# samd21_sensorhub_1_1_jan2022.net
KiCad netlist of a schematic drawn in EAGLE
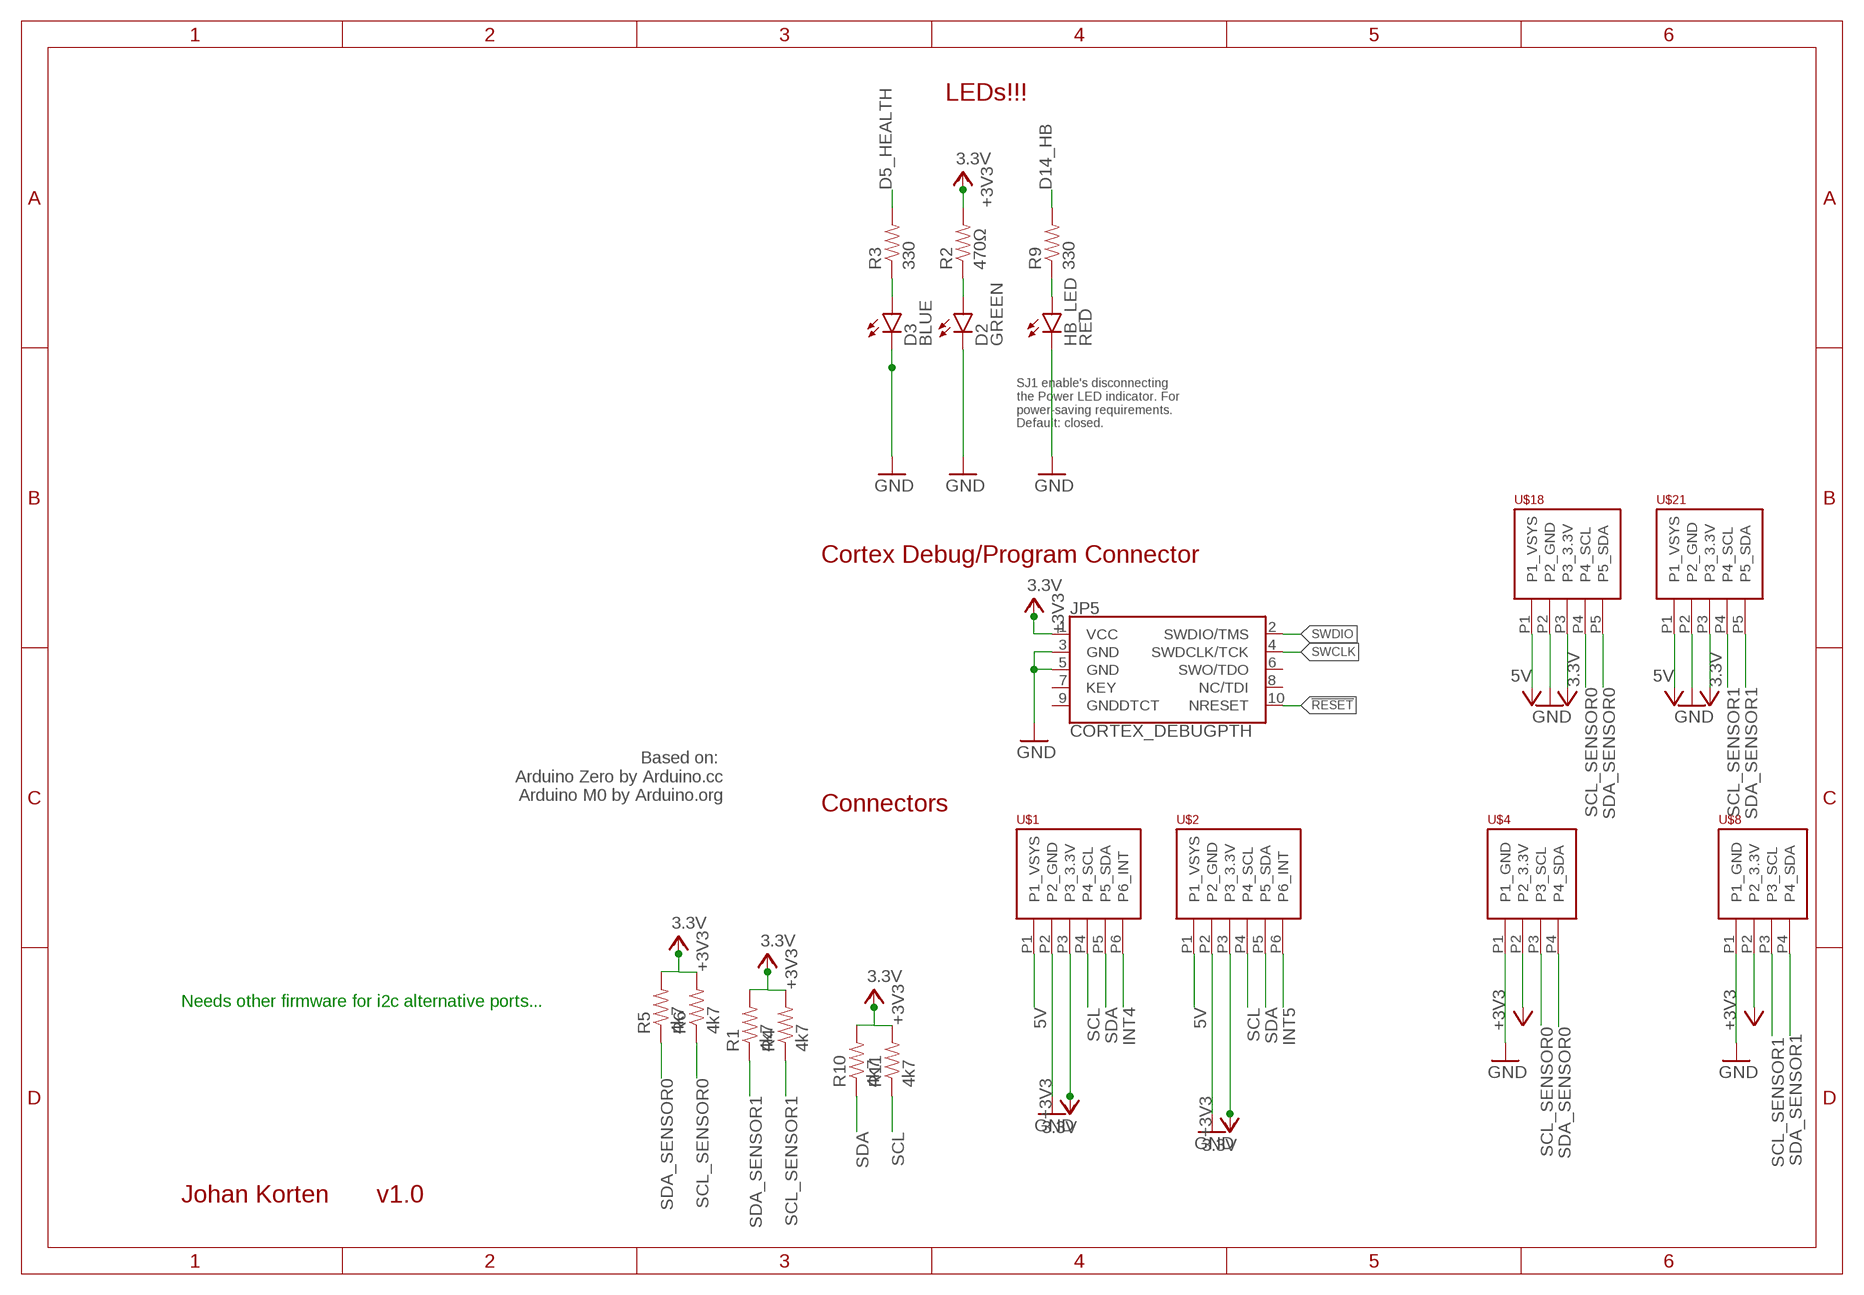
[diagram p0: schematic, sheet 1]
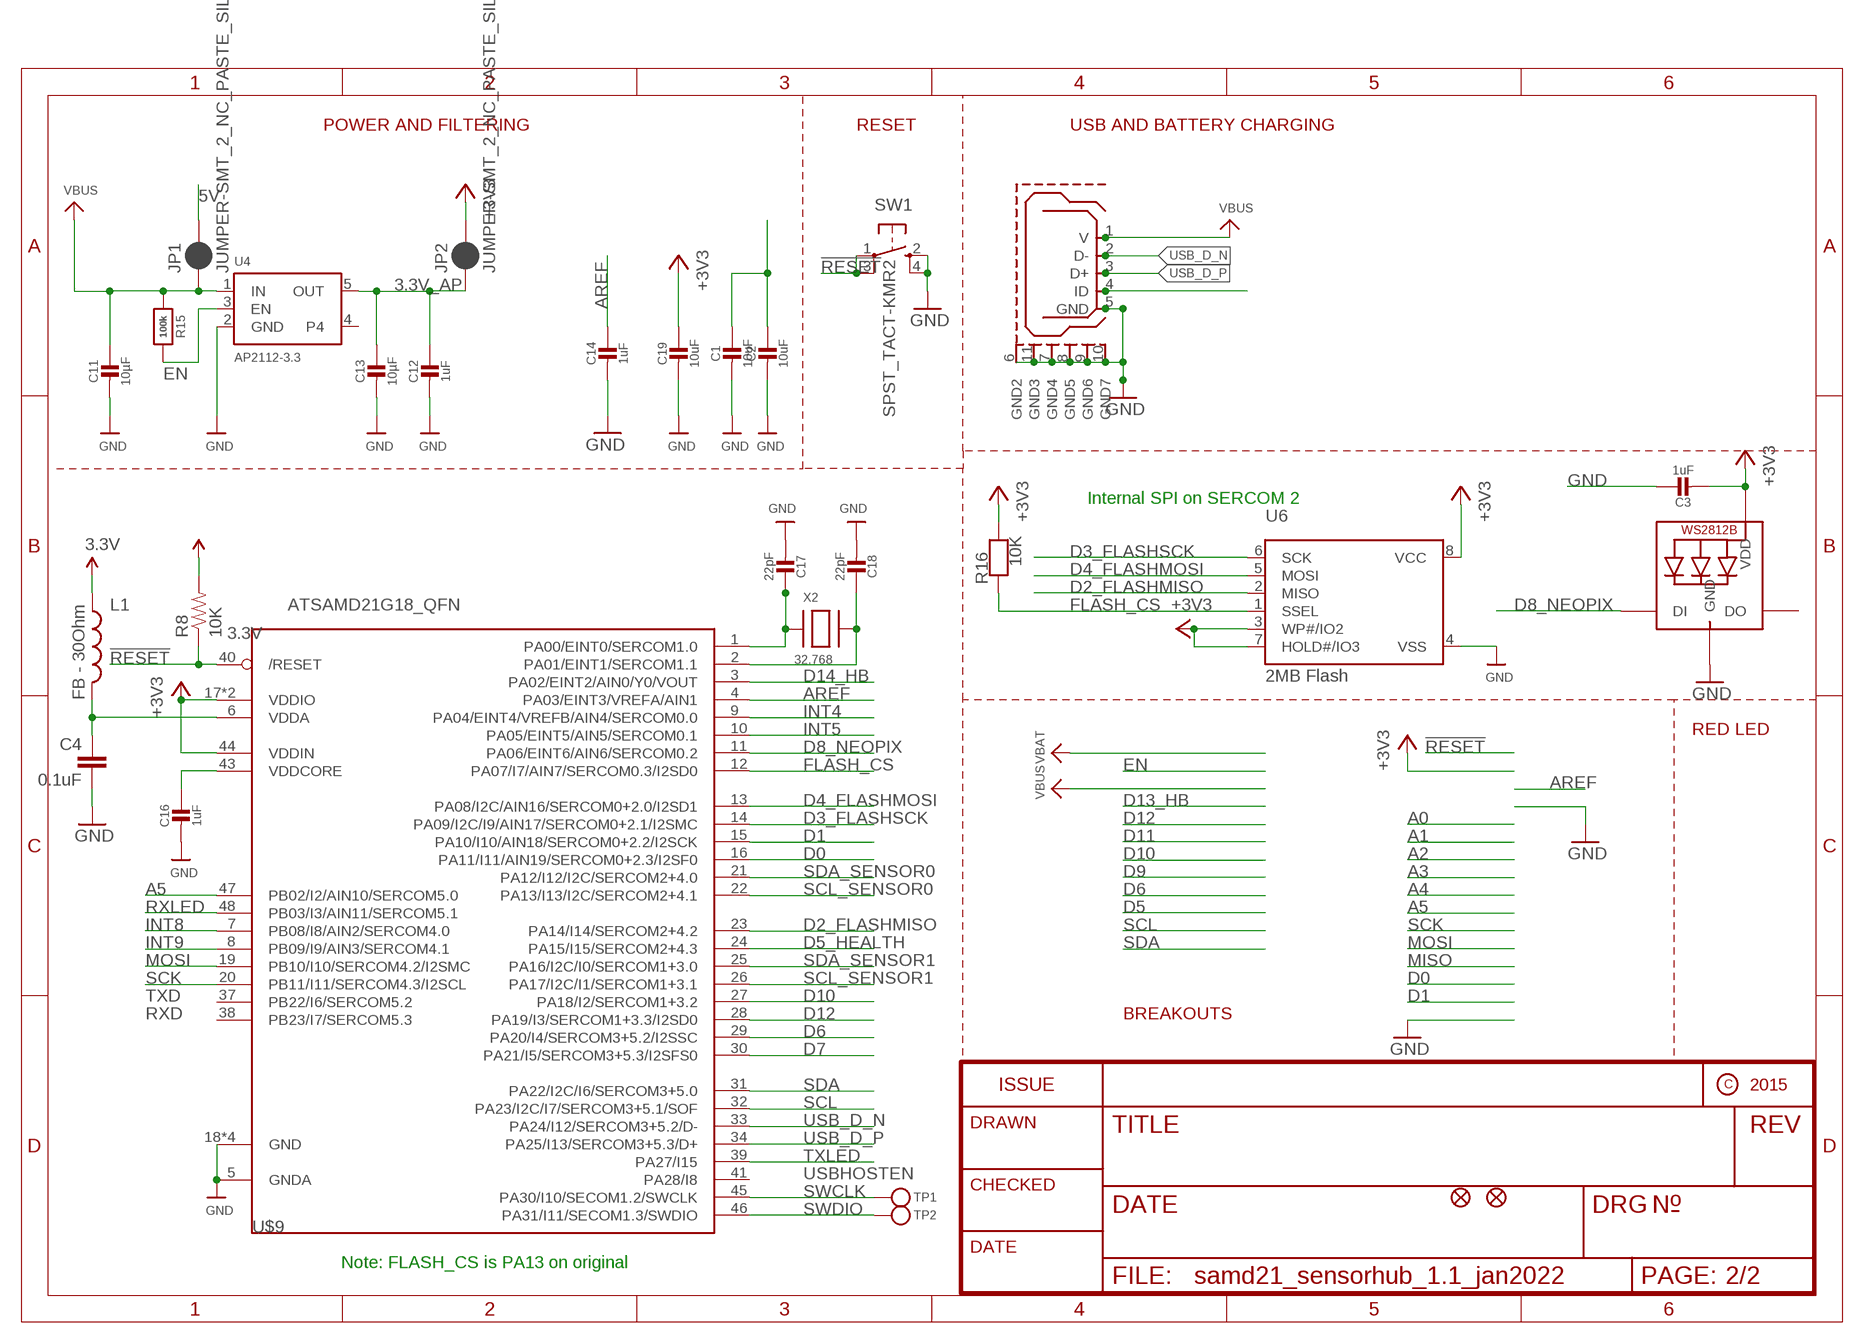
[diagram p1: schematic, sheet 2]

(export (version "E")
  (design (tool "Eeschema 10.0.6"))
  (components
    (comp (ref "D2")
      (value "GREEN")
      (footprint "eagle-import:LED-0603")
      (libsource (lib "eagle-import") (part "LED-RED0603"))
    )
    (comp (ref "D3")
      (value "BLUE")
      (footprint "eagle-import:LED-0603")
      (libsource (lib "eagle-import") (part "LED-BLUE0603"))
    )
    (comp (ref "HB_LED")
      (value "RED")
      (footprint "eagle-import:LED-0603")
      (libsource (lib "eagle-import") (part "LED-RED0603"))
    )
    (comp (ref "JP5")
      (value "CORTEX_DEBUGPTH")
      (footprint "eagle-import:2X5-PTH-1.27MM")
      (libsource (lib "eagle-import") (part "CORTEX_DEBUGPTH"))
    )
    (comp (ref "R1")
      (value "4k7")
      (footprint "eagle-import:0603-RES")
      (libsource (lib "eagle-import") (part "330OHM1/10W1%(0603)"))
    )
    (comp (ref "R2")
      (value "470Ω")
      (footprint "eagle-import:0603-RES")
      (libsource (lib "eagle-import") (part "330OHM1/10W1%(0603)"))
    )
    (comp (ref "R3")
      (value "330")
      (footprint "eagle-import:0603-RES")
      (libsource (lib "eagle-import") (part "330OHM1/10W1%(0603)"))
    )
    (comp (ref "R4")
      (value "4k7")
      (footprint "eagle-import:0603-RES")
      (libsource (lib "eagle-import") (part "330OHM1/10W1%(0603)"))
    )
    (comp (ref "R5")
      (value "4k7")
      (footprint "eagle-import:0603-RES")
      (libsource (lib "eagle-import") (part "330OHM1/10W1%(0603)"))
    )
    (comp (ref "R6")
      (value "4k7")
      (footprint "eagle-import:0603-RES")
      (libsource (lib "eagle-import") (part "330OHM1/10W1%(0603)"))
    )
    (comp (ref "R9")
      (value "330")
      (footprint "eagle-import:0603-RES")
      (libsource (lib "eagle-import") (part "330OHM1/10W1%(0603)"))
    )
    (comp (ref "R10")
      (value "4k7")
      (footprint "eagle-import:0603-RES")
      (libsource (lib "eagle-import") (part "330OHM1/10W1%(0603)"))
    )
    (comp (ref "R11")
      (value "4k7")
      (footprint "eagle-import:0603-RES")
      (libsource (lib "eagle-import") (part "330OHM1/10W1%(0603)"))
    )
    (comp (ref "U$1")
      (value "PHOENIX_PTSM_M6_TH_I2CPPANGLE")
      (footprint "eagle-import:PTSM_M6_THRHOLE")
      (libsource (lib "eagle-import") (part "PHOENIX_PTSM_M6_TH_I2CPPANGLE"))
    )
    (comp (ref "U$2")
      (value "PHOENIX_PTSM_M6_TH_I2CPPANGLE")
      (footprint "eagle-import:PTSM_M6_THRHOLE")
      (libsource (lib "eagle-import") (part "PHOENIX_PTSM_M6_TH_I2CPPANGLE"))
    )
    (comp (ref "U$4")
      (value "PHOENIX_PTSM_M4_THANGLE")
      (footprint "eagle-import:PTSM_M4_TH")
      (libsource (lib "eagle-import") (part "PHOENIX_PTSM_M4_THANGLE"))
    )
    (comp (ref "U$8")
      (value "PHOENIX_PTSM_M4_THANGLE")
      (footprint "eagle-import:PTSM_M4_TH")
      (libsource (lib "eagle-import") (part "PHOENIX_PTSM_M4_THANGLE"))
    )
    (comp (ref "U$18")
      (value "PHOENIX_PTSM_M5_TH_I2C++")
      (footprint "eagle-import:PTSM_M5_THRHOLE")
      (libsource (lib "eagle-import") (part "PHOENIX_PTSM_M5_TH_I2C++"))
    )
    (comp (ref "U$21")
      (value "PHOENIX_PTSM_M5_TH_I2C++")
      (footprint "eagle-import:PTSM_M5_THRHOLE")
      (libsource (lib "eagle-import") (part "PHOENIX_PTSM_M5_TH_I2C++"))
    )
    (comp (ref "C1")
      (value "10uF")
      (footprint "eagle-import:0805-NO")
      (libsource (lib "eagle-import") (part "CAP_CERAMIC0805-NOOUTLINE"))
    )
    (comp (ref "C2")
      (value "10uF")
      (footprint "eagle-import:0805-NO")
      (libsource (lib "eagle-import") (part "CAP_CERAMIC0805-NOOUTLINE"))
    )
    (comp (ref "C3")
      (value "1uF")
      (footprint "eagle-import:0603-NO")
      (libsource (lib "eagle-import") (part "CAP_CERAMIC0603_NO"))
    )
    (comp (ref "C4")
      (value "0.1uF")
      (footprint "eagle-import:0402-CAP")
      (libsource (lib "eagle-import") (part "0.1UF-16V(+-10%)(0402)"))
    )
    (comp (ref "C11")
      (value "10µF")
      (footprint "eagle-import:0805-NO")
      (libsource (lib "eagle-import") (part "CAP_CERAMIC0805-NOOUTLINE"))
    )
    (comp (ref "C12")
      (value "1uF")
      (footprint "eagle-import:0603-NO")
      (libsource (lib "eagle-import") (part "CAP_CERAMIC0603_NO"))
    )
    (comp (ref "C13")
      (value "10µF")
      (footprint "eagle-import:0805-NO")
      (libsource (lib "eagle-import") (part "CAP_CERAMIC0805-NOOUTLINE"))
    )
    (comp (ref "C14")
      (value "1uF")
      (footprint "eagle-import:0603-NO")
      (libsource (lib "eagle-import") (part "CAP_CERAMIC0603_NO"))
    )
    (comp (ref "C16")
      (value "1uF")
      (footprint "eagle-import:0603-NO")
      (libsource (lib "eagle-import") (part "CAP_CERAMIC0603_NO"))
    )
    (comp (ref "C17")
      (value "22pF")
      (footprint "eagle-import:0603-NO")
      (libsource (lib "eagle-import") (part "CAP_CERAMIC0603_NO"))
    )
    (comp (ref "C18")
      (value "22pF")
      (footprint "eagle-import:0603-NO")
      (libsource (lib "eagle-import") (part "CAP_CERAMIC0603_NO"))
    )
    (comp (ref "C19")
      (value "10uF")
      (footprint "eagle-import:0805-NO")
      (libsource (lib "eagle-import") (part "CAP_CERAMIC0805-NOOUTLINE"))
    )
    (comp (ref "JP1")
      (value "JUMPER-SMT_2_NC_PASTE_SILK")
      (footprint "eagle-import:SMT-JUMPER_2_NC_PASTE_SILK")
      (libsource (lib "eagle-import") (part "JUMPER-SMT_2_NC_PASTE_SILK"))
    )
    (comp (ref "JP2")
      (value "JUMPER-SMT_2_NC_PASTE_SILK")
      (footprint "eagle-import:SMT-JUMPER_2_NC_PASTE_SILK")
      (libsource (lib "eagle-import") (part "JUMPER-SMT_2_NC_PASTE_SILK"))
    )
    (comp (ref "L1")
      (value "FB - 30Ohm")
      (footprint "eagle-import:0603")
      (libsource (lib "eagle-import") (part "INDUCTOR0603"))
    )
    (comp (ref "LED1")
      (value "WS2812B3535")
      (footprint "eagle-import:LED3535")
      (libsource (lib "eagle-import") (part "WS2812B3535"))
    )
    (comp (ref "R8")
      (value "10K")
      (footprint "eagle-import:0603-RES")
      (libsource (lib "eagle-import") (part "10KOHM-1/10W-1%(0603)0603"))
    )
    (comp (ref "R15")
      (value "100k")
      (footprint "eagle-import:0603-NO")
      (libsource (lib "eagle-import") (part "RESISTOR_0603_NOOUT"))
    )
    (comp (ref "R16")
      (value "10K")
      (footprint "eagle-import:0603-NO")
      (libsource (lib "eagle-import") (part "RESISTOR_0603_NOOUT"))
    )
    (comp (ref "SW1")
      (value "SPST_TACT-KMR2")
      (footprint "eagle-import:KMR2")
      (libsource (lib "eagle-import") (part "SPST_TACT-KMR2"))
    )
    (comp (ref "TP1")
      (value "TESTPOINTROUND1.5MM")
      (footprint "eagle-import:TESTPOINT_ROUND_1.5MM")
      (libsource (lib "eagle-import") (part "TESTPOINTROUND1.5MM"))
    )
    (comp (ref "TP2")
      (value "TESTPOINTROUND1.5MM")
      (footprint "eagle-import:TESTPOINT_ROUND_1.5MM")
      (libsource (lib "eagle-import") (part "TESTPOINTROUND1.5MM"))
    )
    (comp (ref "U$6")
      (value "USB_MICROB")
      (footprint "eagle-import:USB_MICROB_PACKAGE")
      (libsource (lib "eagle-import") (part "USB_MICROB"))
    )
    (comp (ref "U$9")
      (value "ATSAMD21G18_QFN")
      (footprint "eagle-import:TQFN48_7MM")
      (libsource (lib "eagle-import") (part "ATSAMD21G_QFN"))
    )
    (comp (ref "U$34")
      (value "FIDUCIAL\"\"")
      (footprint "eagle-import:FIDUCIAL_1MM")
      (libsource (lib "eagle-import") (part "FIDUCIAL{dblquote}{dblquote}"))
    )
    (comp (ref "U$35")
      (value "FIDUCIAL\"\"")
      (footprint "eagle-import:FIDUCIAL_1MM")
      (libsource (lib "eagle-import") (part "FIDUCIAL{dblquote}{dblquote}"))
    )
    (comp (ref "U4")
      (value "AP2112-3.3")
      (footprint "eagle-import:SOT23-5")
      (libsource (lib "eagle-import") (part "VREG_SOT23-5"))
    )
    (comp (ref "U6")
      (value "2MB Flash")
      (footprint "eagle-import:SOIC8_208MIL")
      (libsource (lib "eagle-import") (part "SPIFLASH_SOIC8208MIL"))
    )
    (comp (ref "X2")
      (value "32.768")
      (footprint "eagle-import:XTAL3215")
      (libsource (lib "eagle-import") (part "XTAL-3.2X1.5"))
    )
  )
  (nets
    (net (code "1") (name "3.3V") (class "Default")
      (node (ref "C19") (pin "1") (pinfunction "1_1") (pintype "passive"))
      (node (ref "C3") (pin "2") (pinfunction "2_2") (pintype "passive"))
      (node (ref "JP2") (pin "2") (pinfunction "2_2") (pintype "passive"))
      (node (ref "JP5") (pin "1") (pinfunction "VCC_1") (pintype "bidirectional"))
      (node (ref "L1") (pin "1") (pinfunction "1_1") (pintype "passive"))
      (node (ref "LED1") (pin "2") (pinfunction "VDD_2") (pintype "power_in"))
      (node (ref "R1") (pin "2") (pinfunction "2_2") (pintype "passive"))
      (node (ref "R10") (pin "2") (pinfunction "2_2") (pintype "passive"))
      (node (ref "R11") (pin "2") (pinfunction "2_2") (pintype "passive"))
      (node (ref "R16") (pin "2") (pinfunction "2_2") (pintype "passive"))
      (node (ref "R2") (pin "2") (pinfunction "2_2") (pintype "passive"))
      (node (ref "R4") (pin "2") (pinfunction "2_2") (pintype "passive"))
      (node (ref "R5") (pin "2") (pinfunction "2_2") (pintype "passive"))
      (node (ref "R6") (pin "2") (pinfunction "2_2") (pintype "passive"))
      (node (ref "R8") (pin "2") (pinfunction "2_2") (pintype "passive"))
      (node (ref "U$1") (pin "P3") (pinfunction "P3_3.3V_P3") (pintype "power_in"))
      (node (ref "U$18") (pin "P3") (pinfunction "P3_3.3V_P3") (pintype "power_in"))
      (node (ref "U$2") (pin "P3") (pinfunction "P3_3.3V_P3") (pintype "power_in"))
      (node (ref "U$21") (pin "P3") (pinfunction "P3_3.3V_P3") (pintype "power_in"))
      (node (ref "U$4") (pin "P2") (pinfunction "P2_3.3V_P2") (pintype "power_in"))
      (node (ref "U$8") (pin "P2") (pinfunction "P2_3.3V_P2") (pintype "power_in"))
      (node (ref "U$9") (pin "17") (pinfunction "VDDIO_17") (pintype "power_in"))
      (node (ref "U$9") (pin "36") (pinfunction "VDDIO_36") (pintype "power_in"))
      (node (ref "U$9") (pin "44") (pinfunction "VDDIN_44") (pintype "power_in"))
      (node (ref "U6") (pin "3") (pinfunction "WP#/IO2_3") (pintype "bidirectional"))
      (node (ref "U6") (pin "7") (pinfunction "HOLD#/IO3_7") (pintype "bidirectional"))
      (node (ref "U6") (pin "8") (pinfunction "VCC_8") (pintype "bidirectional"))
    )
    (net (code "2") (name "3.3V_AP") (class "Default")
      (node (ref "C12") (pin "1") (pinfunction "1_1") (pintype "passive"))
      (node (ref "C13") (pin "1") (pinfunction "1_1") (pintype "passive"))
      (node (ref "JP2") (pin "1") (pinfunction "1_1") (pintype "passive"))
      (node (ref "U4") (pin "5") (pinfunction "OUT_5") (pintype "power_in"))
    )
    (net (code "3") (name "5V") (class "Default")
      (node (ref "C1") (pin "1") (pinfunction "1_1") (pintype "passive"))
      (node (ref "C2") (pin "1") (pinfunction "1_1") (pintype "passive"))
      (node (ref "JP1") (pin "2") (pinfunction "2_2") (pintype "passive"))
      (node (ref "U$1") (pin "P1") (pinfunction "P1_VSYS_P1") (pintype "power_in"))
      (node (ref "U$18") (pin "P1") (pinfunction "P1_VSYS_P1") (pintype "power_in"))
      (node (ref "U$2") (pin "P1") (pinfunction "P1_VSYS_P1") (pintype "power_in"))
      (node (ref "U$21") (pin "P1") (pinfunction "P1_VSYS_P1") (pintype "power_in"))
    )
    (net (code "9") (name "A5") (class "Default")
      (node (ref "U$9") (pin "47") (pinfunction "PB02/I2/AIN10/SERCOM5.0_47") (pintype "bidirectional"))
    )
    (net (code "10") (name "AREF") (class "Default")
      (node (ref "C14") (pin "1") (pinfunction "1_1") (pintype "passive"))
      (node (ref "U$9") (pin "4") (pinfunction "PA03/EINT3/VREFA/AIN1_4") (pintype "bidirectional"))
    )
    (net (code "11") (name "D0") (class "Default")
      (node (ref "U$9") (pin "16") (pinfunction "PA11/I11/AIN19/SERCOM0+2.3/I2SF0_16") (pintype "bidirectional"))
    )
    (net (code "12") (name "D1") (class "Default")
      (node (ref "U$9") (pin "15") (pinfunction "PA10/I10/AIN18/SERCOM0+2.2/I2SCK_15") (pintype "bidirectional"))
    )
    (net (code "13") (name "D2_FLASHMISO") (class "Default")
      (node (ref "U$9") (pin "23") (pinfunction "PA14/I14/SERCOM2+4.2_23") (pintype "bidirectional"))
      (node (ref "U6") (pin "2") (pinfunction "MISO_2") (pintype "bidirectional"))
    )
    (net (code "14") (name "D3_FLASHSCK") (class "Default")
      (node (ref "U$9") (pin "14") (pinfunction "PA09/I2C/I9/AIN17/SERCOM0+2.1/I2SMC_14") (pintype "bidirectional"))
      (node (ref "U6") (pin "6") (pinfunction "SCK_6") (pintype "bidirectional"))
    )
    (net (code "15") (name "D4_FLASHMOSI") (class "Default")
      (node (ref "U$9") (pin "13") (pinfunction "PA08/I2C/AIN16/SERCOM0+2.0/I2SD1_13") (pintype "bidirectional"))
      (node (ref "U6") (pin "5") (pinfunction "MOSI_5") (pintype "bidirectional"))
    )
    (net (code "17") (name "D5_HEALTH") (class "Default")
      (node (ref "R3") (pin "2") (pinfunction "2_2") (pintype "passive"))
      (node (ref "U$9") (pin "24") (pinfunction "PA15/I15/SERCOM2+4.3_24") (pintype "bidirectional"))
    )
    (net (code "18") (name "D6") (class "Default")
      (node (ref "U$9") (pin "29") (pinfunction "PA20/I4/SERCOM3+5.2/I2SSC_29") (pintype "bidirectional"))
    )
    (net (code "19") (name "D7") (class "Default")
      (node (ref "U$9") (pin "30") (pinfunction "PA21/I5/SERCOM3+5.3/I2SFS0_30") (pintype "bidirectional"))
    )
    (net (code "20") (name "D8_NEOPIX") (class "Default")
      (node (ref "LED1") (pin "1") (pinfunction "DI_1") (pintype "input"))
      (node (ref "U$9") (pin "11") (pinfunction "PA06/EINT6/AIN6/SERCOM0.2_11") (pintype "bidirectional"))
    )
    (net (code "22") (name "D10") (class "Default")
      (node (ref "U$9") (pin "27") (pinfunction "PA18/I2/SERCOM1+3.2_27") (pintype "bidirectional"))
    )
    (net (code "24") (name "D12") (class "Default")
      (node (ref "U$9") (pin "28") (pinfunction "PA19/I3/SERCOM1+3.3/I2SD0_28") (pintype "bidirectional"))
    )
    (net (code "26") (name "D14_HB") (class "Default")
      (node (ref "R9") (pin "2") (pinfunction "2_2") (pintype "passive"))
      (node (ref "U$9") (pin "3") (pinfunction "PA02/EINT2/AIN0/Y0/VOUT_3") (pintype "bidirectional"))
    )
    (net (code "27") (name "EN") (class "Default")
      (node (ref "R15") (pin "2") (pinfunction "2_2") (pintype "passive"))
      (node (ref "U4") (pin "3") (pinfunction "EN_3") (pintype "input"))
    )
    (net (code "28") (name "FLASH_CS") (class "Default")
      (node (ref "R16") (pin "1") (pinfunction "1_1") (pintype "passive"))
      (node (ref "U$9") (pin "12") (pinfunction "PA07/I7/AIN7/SERCOM0.3/I2SD0_12") (pintype "bidirectional"))
      (node (ref "U6") (pin "1") (pinfunction "SSEL_1") (pintype "bidirectional"))
    )
    (net (code "29") (name "GND") (class "Default")
      (node (ref "C1") (pin "2") (pinfunction "2_2") (pintype "passive"))
      (node (ref "C11") (pin "2") (pinfunction "2_2") (pintype "passive"))
      (node (ref "C12") (pin "2") (pinfunction "2_2") (pintype "passive"))
      (node (ref "C13") (pin "2") (pinfunction "2_2") (pintype "passive"))
      (node (ref "C14") (pin "2") (pinfunction "2_2") (pintype "passive"))
      (node (ref "C16") (pin "2") (pinfunction "2_2") (pintype "passive"))
      (node (ref "C17") (pin "2") (pinfunction "2_2") (pintype "passive"))
      (node (ref "C18") (pin "2") (pinfunction "2_2") (pintype "passive"))
      (node (ref "C19") (pin "2") (pinfunction "2_2") (pintype "passive"))
      (node (ref "C2") (pin "2") (pinfunction "2_2") (pintype "passive"))
      (node (ref "C3") (pin "1") (pinfunction "1_1") (pintype "passive"))
      (node (ref "C4") (pin "2") (pinfunction "2_2") (pintype "passive"))
      (node (ref "D2") (pin "C") (pinfunction "C_C") (pintype "passive"))
      (node (ref "D3") (pin "C") (pinfunction "C_C") (pintype "passive"))
      (node (ref "HB_LED") (pin "C") (pinfunction "C_C") (pintype "passive"))
      (node (ref "JP5") (pin "3") (pinfunction "GND_3") (pintype "bidirectional"))
      (node (ref "JP5") (pin "5") (pinfunction "GND_5") (pintype "bidirectional"))
      (node (ref "LED1") (pin "4") (pinfunction "GND_4") (pintype "power_in"))
      (node (ref "SW1") (pin "2") (pinfunction "S_2") (pintype "passive"))
      (node (ref "SW1") (pin "4") (pinfunction "S1_4") (pintype "passive"))
      (node (ref "U$1") (pin "P2") (pinfunction "P2_GND_P2") (pintype "power_in"))
      (node (ref "U$18") (pin "P2") (pinfunction "P2_GND_P2") (pintype "power_in"))
      (node (ref "U$2") (pin "P2") (pinfunction "P2_GND_P2") (pintype "power_in"))
      (node (ref "U$21") (pin "P2") (pinfunction "P2_GND_P2") (pintype "power_in"))
      (node (ref "U$4") (pin "P1") (pinfunction "P1_GND_P1") (pintype "power_in"))
      (node (ref "U$6") (pin "10") (pinfunction "GND7_10") (pintype "bidirectional"))
      (node (ref "U$6") (pin "11") (pinfunction "GND3_11") (pintype "bidirectional"))
      (node (ref "U$6") (pin "5") (pinfunction "GND_5") (pintype "bidirectional"))
      (node (ref "U$6") (pin "6") (pinfunction "GND2_6") (pintype "bidirectional"))
      (node (ref "U$6") (pin "7") (pinfunction "GND4_7") (pintype "bidirectional"))
      (node (ref "U$6") (pin "8") (pinfunction "GND5_8") (pintype "bidirectional"))
      (node (ref "U$6") (pin "9") (pinfunction "GND6_9") (pintype "bidirectional"))
      (node (ref "U$8") (pin "P1") (pinfunction "P1_GND_P1") (pintype "power_in"))
      (node (ref "U$9") (pin "18") (pinfunction "GND_18") (pintype "power_in"))
      (node (ref "U$9") (pin "35") (pinfunction "GND_35") (pintype "power_in"))
      (node (ref "U$9") (pin "42") (pinfunction "GND_42") (pintype "power_in"))
      (node (ref "U$9") (pin "5") (pinfunction "GNDA_5") (pintype "power_in"))
      (node (ref "U$9") (pin "THERMAL") (pinfunction "GND_THERMAL") (pintype "power_in"))
      (node (ref "U4") (pin "2") (pinfunction "GND_2") (pintype "power_in"))
      (node (ref "U6") (pin "4") (pinfunction "VSS_4") (pintype "bidirectional"))
    )
    (net (code "30") (name "INT4") (class "Default")
      (node (ref "U$1") (pin "P6") (pinfunction "P6_INT_P6") (pintype "power_in"))
      (node (ref "U$9") (pin "9") (pinfunction "PA04/EINT4/VREFB/AIN4/SERCOM0.0_9") (pintype "bidirectional"))
    )
    (net (code "31") (name "INT5") (class "Default")
      (node (ref "U$2") (pin "P6") (pinfunction "P6_INT_P6") (pintype "power_in"))
      (node (ref "U$9") (pin "10") (pinfunction "PA05/EINT5/AIN5/SERCOM0.1_10") (pintype "bidirectional"))
    )
    (net (code "32") (name "INT8") (class "Default")
      (node (ref "U$9") (pin "7") (pinfunction "PB08/I8/AIN2/SERCOM4.0_7") (pintype "bidirectional"))
    )
    (net (code "33") (name "INT9") (class "Default")
      (node (ref "U$9") (pin "8") (pinfunction "PB09/I9/AIN3/SERCOM4.1_8") (pintype "bidirectional"))
    )
    (net (code "35") (name "MOSI") (class "Default")
      (node (ref "U$9") (pin "19") (pinfunction "PB10/I10/SERCOM4.2/I2SMC_19") (pintype "bidirectional"))
    )
    (net (code "36") (name "Net-(D2-PadA)") (class "Default")
      (node (ref "D2") (pin "A") (pinfunction "A_A") (pintype "passive"))
      (node (ref "R2") (pin "1") (pinfunction "1_1") (pintype "passive"))
    )
    (net (code "37") (name "Net-(D3-PadA)") (class "Default")
      (node (ref "D3") (pin "A") (pinfunction "A_A") (pintype "passive"))
      (node (ref "R3") (pin "1") (pinfunction "1_1") (pintype "passive"))
    )
    (net (code "38") (name "Net-(HB_LED-PadA)") (class "Default")
      (node (ref "HB_LED") (pin "A") (pinfunction "A_A") (pintype "passive"))
      (node (ref "R9") (pin "1") (pinfunction "1_1") (pintype "passive"))
    )
    (net (code "39") (name "Net-(U$9-PA00{slash}EINT0{slash}SERCOM1.0)") (class "Default")
      (node (ref "C17") (pin "1") (pinfunction "1_1") (pintype "passive"))
      (node (ref "U$9") (pin "1") (pinfunction "PA00/EINT0/SERCOM1.0_1") (pintype "bidirectional"))
      (node (ref "X2") (pin "P$1") (pinfunction "P$1_P$1") (pintype "bidirectional"))
    )
    (net (code "40") (name "Net-(U$9-PA01{slash}EINT1{slash}SERCOM1.1)") (class "Default")
      (node (ref "C18") (pin "1") (pinfunction "1_1") (pintype "passive"))
      (node (ref "U$9") (pin "2") (pinfunction "PA01/EINT1/SERCOM1.1_2") (pintype "bidirectional"))
      (node (ref "X2") (pin "P$2") (pinfunction "P$2_P$2") (pintype "bidirectional"))
    )
    (net (code "41") (name "Net-(U$9-VDDA)") (class "Default")
      (node (ref "C4") (pin "1") (pinfunction "1_1") (pintype "passive"))
      (node (ref "L1") (pin "2") (pinfunction "2_2") (pintype "passive"))
      (node (ref "U$9") (pin "6") (pinfunction "VDDA_6") (pintype "power_in"))
    )
    (net (code "42") (name "Net-(U$9-VDDCORE)") (class "Default")
      (node (ref "C16") (pin "1") (pinfunction "1_1") (pintype "passive"))
      (node (ref "U$9") (pin "43") (pinfunction "VDDCORE_43") (pintype "power_in"))
    )
    (net (code "43") (name "RXLED") (class "Default")
      (node (ref "U$9") (pin "48") (pinfunction "PB03/I3/AIN11/SERCOM5.1_48") (pintype "bidirectional"))
    )
    (net (code "44") (name "SCK") (class "Default")
      (node (ref "U$9") (pin "20") (pinfunction "PB11/I11/SERCOM4.3/I2SCL_20") (pintype "bidirectional"))
    )
    (net (code "45") (name "SCL") (class "Default")
      (node (ref "R11") (pin "1") (pinfunction "1_1") (pintype "passive"))
      (node (ref "U$1") (pin "P4") (pinfunction "P4_SCL_P4") (pintype "bidirectional"))
      (node (ref "U$2") (pin "P4") (pinfunction "P4_SCL_P4") (pintype "bidirectional"))
      (node (ref "U$9") (pin "32") (pinfunction "PA23/I2C/I7/SERCOM3+5.1/SOF_32") (pintype "bidirectional"))
    )
    (net (code "46") (name "SCL_SENSOR0") (class "Default")
      (node (ref "R6") (pin "1") (pinfunction "1_1") (pintype "passive"))
      (node (ref "U$18") (pin "P4") (pinfunction "P4_SCL_P4") (pintype "bidirectional"))
      (node (ref "U$4") (pin "P3") (pinfunction "P3_SCL_P3") (pintype "bidirectional"))
      (node (ref "U$9") (pin "22") (pinfunction "PA13/I13/I2C/SERCOM2+4.1_22") (pintype "bidirectional"))
    )
    (net (code "47") (name "SCL_SENSOR1") (class "Default")
      (node (ref "R4") (pin "1") (pinfunction "1_1") (pintype "passive"))
      (node (ref "U$21") (pin "P4") (pinfunction "P4_SCL_P4") (pintype "bidirectional"))
      (node (ref "U$8") (pin "P3") (pinfunction "P3_SCL_P3") (pintype "bidirectional"))
      (node (ref "U$9") (pin "26") (pinfunction "PA17/I2C/I1/SERCOM1+3.1_26") (pintype "bidirectional"))
    )
    (net (code "48") (name "SDA") (class "Default")
      (node (ref "R10") (pin "1") (pinfunction "1_1") (pintype "passive"))
      (node (ref "U$1") (pin "P5") (pinfunction "P5_SDA_P5") (pintype "bidirectional"))
      (node (ref "U$2") (pin "P5") (pinfunction "P5_SDA_P5") (pintype "bidirectional"))
      (node (ref "U$9") (pin "31") (pinfunction "PA22/I2C/I6/SERCOM3+5.0_31") (pintype "bidirectional"))
    )
    (net (code "49") (name "SDA_SENSOR0") (class "Default")
      (node (ref "R5") (pin "1") (pinfunction "1_1") (pintype "passive"))
      (node (ref "U$18") (pin "P5") (pinfunction "P5_SDA_P5") (pintype "bidirectional"))
      (node (ref "U$4") (pin "P4") (pinfunction "P4_SDA_P4") (pintype "bidirectional"))
      (node (ref "U$9") (pin "21") (pinfunction "PA12/I12/I2C/SERCOM2+4.0_21") (pintype "bidirectional"))
    )
    (net (code "50") (name "SDA_SENSOR1") (class "Default")
      (node (ref "R1") (pin "1") (pinfunction "1_1") (pintype "passive"))
      (node (ref "U$21") (pin "P5") (pinfunction "P5_SDA_P5") (pintype "bidirectional"))
      (node (ref "U$8") (pin "P4") (pinfunction "P4_SDA_P4") (pintype "bidirectional"))
      (node (ref "U$9") (pin "25") (pinfunction "PA16/I2C/I0/SERCOM1+3.0_25") (pintype "bidirectional"))
    )
    (net (code "51") (name "SWCLK") (class "Default")
      (node (ref "JP5") (pin "4") (pinfunction "SWDCLK/TCK_4") (pintype "bidirectional"))
      (node (ref "TP1") (pin "P$1") (pinfunction "P$1_P$1") (pintype "bidirectional"))
      (node (ref "U$9") (pin "45") (pinfunction "PA30/I10/SECOM1.2/SWCLK_45") (pintype "bidirectional"))
    )
    (net (code "52") (name "SWDIO") (class "Default")
      (node (ref "JP5") (pin "2") (pinfunction "SWDIO/TMS_2") (pintype "bidirectional"))
      (node (ref "TP2") (pin "P$1") (pinfunction "P$1_P$1") (pintype "bidirectional"))
      (node (ref "U$9") (pin "46") (pinfunction "PA31/I11/SECOM1.3/SWDIO_46") (pintype "bidirectional"))
    )
    (net (code "53") (name "TXLED") (class "Default")
      (node (ref "U$9") (pin "39") (pinfunction "PA27/I15_39") (pintype "bidirectional"))
    )
    (net (code "54") (name "USB_D_N") (class "Default")
      (node (ref "U$6") (pin "2") (pinfunction "D-_2") (pintype "bidirectional"))
      (node (ref "U$9") (pin "33") (pinfunction "PA24/I12/SERCOM3+5.2/D-_33") (pintype "bidirectional"))
    )
    (net (code "55") (name "USB_D_P") (class "Default")
      (node (ref "U$6") (pin "3") (pinfunction "D+_3") (pintype "bidirectional"))
      (node (ref "U$9") (pin "34") (pinfunction "PA25/I13/SERCOM3+5.3/D+_34") (pintype "bidirectional"))
    )
    (net (code "57") (name "VBUS") (class "Default")
      (node (ref "C11") (pin "1") (pinfunction "1_1") (pintype "passive"))
      (node (ref "JP1") (pin "1") (pinfunction "1_1") (pintype "passive"))
      (node (ref "R15") (pin "1") (pinfunction "1_1") (pintype "passive"))
      (node (ref "U$6") (pin "1") (pinfunction "V_1") (pintype "bidirectional"))
      (node (ref "U4") (pin "1") (pinfunction "IN_1") (pintype "power_in"))
    )
    (net (code "58") (name "unconnected-(JP5-GNDDTCT-Pad9)") (class "Default")
      (node (ref "JP5") (pin "9") (pinfunction "GNDDTCT_9") (pintype "bidirectional"))
    )
    (net (code "59") (name "unconnected-(JP5-KEY-Pad7)") (class "Default")
      (node (ref "JP5") (pin "7") (pinfunction "KEY_7") (pintype "bidirectional"))
    )
    (net (code "60") (name "unconnected-(JP5-NC{slash}TDI-Pad8)") (class "Default")
      (node (ref "JP5") (pin "8") (pinfunction "NC/TDI_8") (pintype "bidirectional"))
    )
    (net (code "61") (name "unconnected-(JP5-SWO{slash}TDO-Pad6)") (class "Default")
      (node (ref "JP5") (pin "6") (pinfunction "SWO/TDO_6") (pintype "bidirectional"))
    )
    (net (code "62") (name "unconnected-(LED1-DO-Pad3)") (class "Default")
      (node (ref "LED1") (pin "3") (pinfunction "DO_3") (pintype "output"))
    )
    (net (code "63") (name "unconnected-(U$6-ID-Pad4)") (class "Default")
      (node (ref "U$6") (pin "4") (pinfunction "ID_4") (pintype "bidirectional"))
    )
    (net (code "64") (name "unconnected-(U$9-PA28{slash}I8-Pad41)") (class "Default")
      (node (ref "U$9") (pin "41") (pinfunction "PA28/I8_41") (pintype "bidirectional"))
    )
    (net (code "65") (name "unconnected-(U$9-PB22{slash}I6{slash}SERCOM5.2-Pad37)") (class "Default")
      (node (ref "U$9") (pin "37") (pinfunction "PB22/I6/SERCOM5.2_37") (pintype "bidirectional"))
    )
    (net (code "66") (name "unconnected-(U$9-PB23{slash}I7{slash}SERCOM5.3-Pad38)") (class "Default")
      (node (ref "U$9") (pin "38") (pinfunction "PB23/I7/SERCOM5.3_38") (pintype "bidirectional"))
    )
    (net (code "67") (name "unconnected-(U4-P4-Pad4)") (class "Default")
      (node (ref "U4") (pin "4") (pinfunction "P4_4") (pintype "bidirectional"))
    )
    (net (code "68") (name "~{RESET}") (class "Default")
      (node (ref "JP5") (pin "10") (pinfunction "NRESET_10") (pintype "bidirectional"))
      (node (ref "R8") (pin "1") (pinfunction "1_1") (pintype "passive"))
      (node (ref "SW1") (pin "1") (pinfunction "P_1") (pintype "passive"))
      (node (ref "SW1") (pin "3") (pinfunction "P1_3") (pintype "passive"))
      (node (ref "U$9") (pin "40") (pinfunction "/RESET_40") (pintype "bidirectional"))
    )
  )
)
